# Connectors_Frontend.net
KiCad netlist of a schematic drawn in Altium Designer
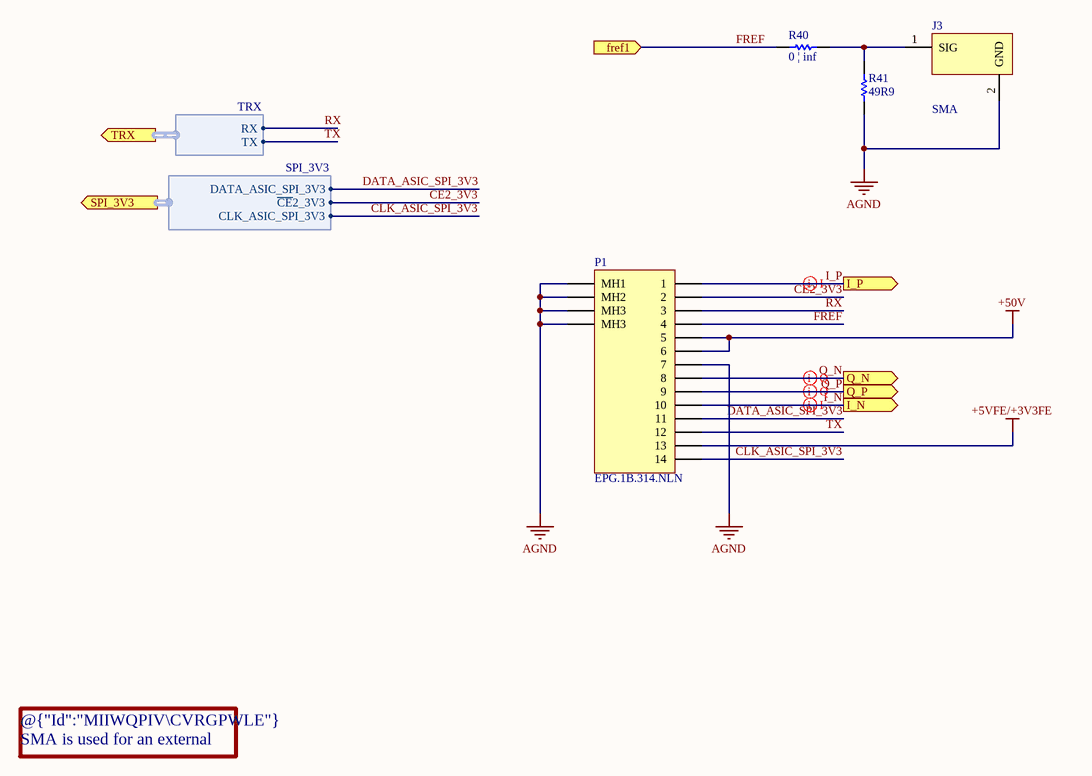
[diagram p0: Connectors_Frontend.SchDoc]

(export (version "E")
  (design (tool "Eeschema 10.0.6"))
  (components
    (comp (ref "J3") (value "SMA") (footprint "SMA") (libsource (lib "IIS-Lib_TW") (part "SMA")))
    (comp (ref "P1")
      (value "EPG.1B.314.NLN")
      (footprint "EPG.1B.314.NLN")
      (libsource (lib "IIS-Lib_TW") (part "EPG.1B.314.NLN"))
    )
    (comp (ref "R40") (value "0 ¦ inf") (footprint "RES_0402") (libsource (lib "IIS-Lib_TW") (part "Res")))
    (comp (ref "R41") (value "49R9") (footprint "RES_0402") (libsource (lib "IIS-Lib_TW") (part "Res")))
  )
  (nets
    (net (code "3") (name "+5VFE{slash}+3V3FE") (class "Default")
      (node (ref "P1") (pin "13") (pinfunction "13_13") (pintype "passive"))
    )
    (net (code "4") (name "+50V") (class "Default")
      (node (ref "P1") (pin "5") (pinfunction "5_5") (pintype "passive"))
      (node (ref "P1") (pin "6") (pinfunction "6_6") (pintype "passive"))
    )
    (net (code "5") (name "/CLK_ASIC_SPI_3V3") (class "Default")
      (node (ref "P1") (pin "14") (pinfunction "14_14") (pintype "passive"))
    )
    (net (code "6") (name "/DATA_ASIC_SPI_3V3") (class "Default")
      (node (ref "P1") (pin "11") (pinfunction "11_11") (pintype "passive"))
    )
    (net (code "7") (name "/FREF") (class "Default")
      (node (ref "P1") (pin "4") (pinfunction "4_4") (pintype "passive"))
      (node (ref "R40") (pin "1") (pinfunction "1_1") (pintype "passive"))
    )
    (net (code "8") (name "/I_N") (class "Default")
      (node (ref "P1") (pin "10") (pinfunction "10_10") (pintype "passive"))
    )
    (net (code "9") (name "/I_P") (class "Default")
      (node (ref "P1") (pin "1") (pinfunction "1_1") (pintype "passive"))
    )
    (net (code "10") (name "/Q_N") (class "Default")
      (node (ref "P1") (pin "8") (pinfunction "8_8") (pintype "passive"))
    )
    (net (code "11") (name "/Q_P") (class "Default")
      (node (ref "P1") (pin "9") (pinfunction "9_9") (pintype "passive"))
    )
    (net (code "12") (name "/RX") (class "Default")
      (node (ref "P1") (pin "3") (pinfunction "3_3") (pintype "passive"))
    )
    (net (code "13") (name "/TX") (class "Default")
      (node (ref "P1") (pin "12") (pinfunction "12_12") (pintype "passive"))
    )
    (net (code "16") (name "/~{CE}2_3V3") (class "Default")
      (node (ref "P1") (pin "2") (pinfunction "2_2") (pintype "passive"))
    )
    (net (code "17") (name "AGND") (class "Default")
      (node (ref "J3") (pin "2") (pinfunction "GND_2") (pintype "passive"))
      (node (ref "P1") (pin "15") (pinfunction "MH1_15") (pintype "passive"))
      (node (ref "P1") (pin "16") (pinfunction "MH2_16") (pintype "passive"))
      (node (ref "P1") (pin "17") (pinfunction "MH3_17") (pintype "passive"))
      (node (ref "P1") (pin "18") (pinfunction "MH3_18") (pintype "passive"))
      (node (ref "P1") (pin "7") (pinfunction "7_7") (pintype "passive"))
      (node (ref "R41") (pin "1") (pinfunction "1_1") (pintype "passive"))
    )
    (net (code "18") (name "Net-(J3-SIG)") (class "Default")
      (node (ref "J3") (pin "1") (pinfunction "SIG_1") (pintype "passive"))
      (node (ref "R40") (pin "2") (pinfunction "2_2") (pintype "passive"))
      (node (ref "R41") (pin "2") (pinfunction "2_2") (pintype "passive"))
    )
  )
)
